# TRD.net
KiCad netlist of a schematic drawn in Altium Designer
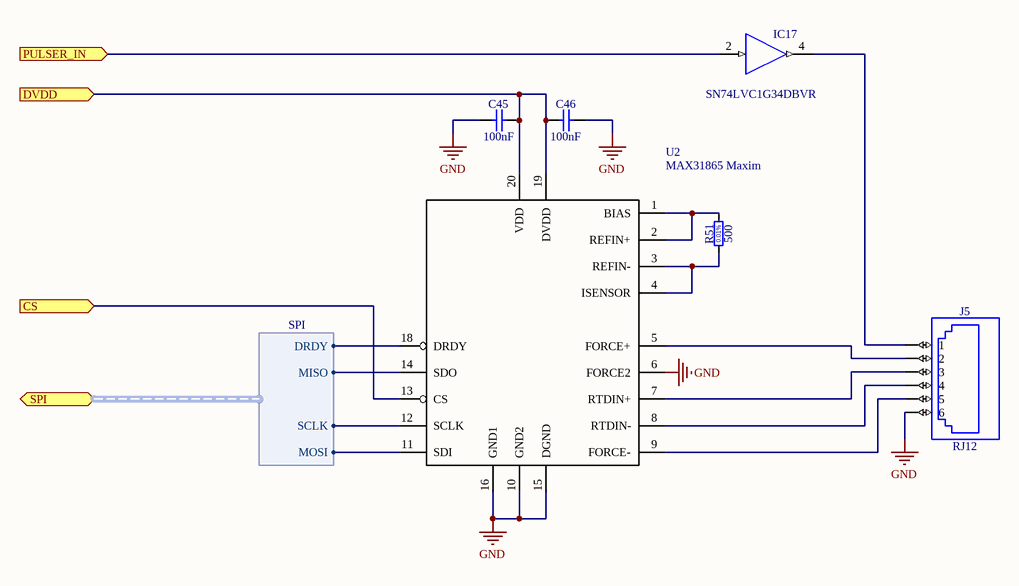
[diagram p0: TRD.SchDoc]

(export (version "E")
  (design (tool "Eeschema 10.0.6"))
  (components
    (comp (ref "C45")
      (value "100nF")
      (footprint "CAPC3216X140N")
      (description "Non-polarised capacitor")
      (fields
        (field (name "PART NUMBER") "CC1206_100NF_100V_10%_X7R")
        (field (name "VOLTAGE") "100V")
        (field (name "AUTHOR") "CERN DEM JLC")
      )
      (libsource (lib "Capacitors") (part "Capacitor - non polarized"))
    )
    (comp (ref "C46")
      (value "100nF")
      (footprint "CAPC3216X140N")
      (description "Non-polarised capacitor")
      (fields
        (field (name "PART NUMBER") "CC1206_100NF_100V_10%_X7R")
        (field (name "VOLTAGE") "100V")
        (field (name "AUTHOR") "CERN DEM JLC")
      )
      (libsource (lib "Capacitors") (part "Capacitor - non polarized"))
    )
    (comp (ref "IC17")
      (value "SN74LVC1G34DBVR")
      (footprint "SOT95P280X145-5N")
      (description "Single Buffer Gate")
      (fields (field (name "MANUFACTURER") "TEXAS INSTRUMENTS") (field (name "AUTHOR") "CERN DEM JLC"))
      (libsource (lib "ICs And Semiconductors") (part "741G34"))
    )
    (comp (ref "J5")
      (value "RJ12")
      (footprint "WURTH_615006138521")
      (description "Connector RJ12 (6P6C)")
      (fields
        (field (name "PART NUMBER") "WURTH_615006138521")
        (field (name "MANUFACTURER") "WURTH ELEKTRONIK")
        (field (name "AUTHOR") "CERN DEM MR")
      )
      (libsource (lib "Connectors") (part "Connector RJ12"))
    )
    (comp (ref "R51")
      (value "500")
      (footprint "RESC2013X64N")
      (description "Resistor - 0.01%")
      (fields
        (field (name "PART NUMBER") "R0805_500R_0.01%_0.2W_0.2PPM_VISHAY_VSMP")
        (field (name "POWER") "0.2W")
        (field (name "AUTHOR") "CERN DEM JLC")
      )
      (libsource (lib "Resistors") (part "Resistor - 0.01%"))
    )
    (comp (ref "U2")
      (value "MAX31865 Maxim")
      (fields (field (name "MANUFACTURER") "Maxim"))
      (libsource (lib "Additional") (part "MAX31865"))
    )
  )
  (nets
    (net (code "2") (name "/CS") (class "Default")
      (node (ref "U2") (pin "13") (pinfunction "CS_13") (pintype "passive"))
    )
    (net (code "3") (name "/DRDY") (class "Default")
      (node (ref "U2") (pin "18") (pinfunction "DRDY_18") (pintype "passive"))
    )
    (net (code "4") (name "/DVDD") (class "Default")
      (node (ref "C45") (pin "2") (pinfunction "2_2") (pintype "passive"))
      (node (ref "C46") (pin "1") (pinfunction "1_1") (pintype "passive"))
      (node (ref "U2") (pin "19") (pinfunction "DVDD_19") (pintype "passive"))
      (node (ref "U2") (pin "20") (pinfunction "VDD_20") (pintype "passive"))
    )
    (net (code "5") (name "/MISO") (class "Default")
      (node (ref "U2") (pin "14") (pinfunction "SDO_14") (pintype "passive"))
    )
    (net (code "6") (name "/MOSI") (class "Default")
      (node (ref "U2") (pin "11") (pinfunction "SDI_11") (pintype "passive"))
    )
    (net (code "7") (name "/PULSER_IN") (class "Default")
      (node (ref "IC17") (pin "2") (pinfunction "IN_2") (pintype "input"))
    )
    (net (code "8") (name "/SCLK") (class "Default")
      (node (ref "U2") (pin "12") (pinfunction "SCLK_12") (pintype "passive"))
    )
    (net (code "10") (name "GND") (class "Default")
      (node (ref "C45") (pin "1") (pinfunction "1_1") (pintype "passive"))
      (node (ref "C46") (pin "2") (pinfunction "2_2") (pintype "passive"))
      (node (ref "IC17") (pin "3") (pinfunction "GND_3") (pintype "power_in"))
      (node (ref "J5") (pin "6") (pinfunction "6_6") (pintype "bidirectional"))
      (node (ref "U2") (pin "10") (pinfunction "GND2_10") (pintype "passive"))
      (node (ref "U2") (pin "15") (pinfunction "DGND_15") (pintype "passive"))
      (node (ref "U2") (pin "16") (pinfunction "GND1_16") (pintype "passive"))
      (node (ref "U2") (pin "6") (pinfunction "FORCE2_6") (pintype "passive"))
    )
    (net (code "11") (name "Net-(IC17-OUT)") (class "Default")
      (node (ref "IC17") (pin "4") (pinfunction "OUT_4") (pintype "output"))
      (node (ref "J5") (pin "1") (pinfunction "1_1") (pintype "bidirectional"))
    )
    (net (code "12") (name "Net-(U2-BIAS)") (class "Default")
      (node (ref "R51") (pin "2") (pinfunction "2_2") (pintype "passive"))
      (node (ref "U2") (pin "1") (pinfunction "BIAS_1") (pintype "passive"))
      (node (ref "U2") (pin "2") (pinfunction "REFIN+_2") (pintype "passive"))
    )
    (net (code "13") (name "Net-(U2-FORCE+)") (class "Default")
      (node (ref "J5") (pin "2") (pinfunction "2_2") (pintype "bidirectional"))
      (node (ref "U2") (pin "5") (pinfunction "FORCE+_5") (pintype "passive"))
    )
    (net (code "14") (name "Net-(U2-FORCE-)") (class "Default")
      (node (ref "J5") (pin "5") (pinfunction "5_5") (pintype "bidirectional"))
      (node (ref "U2") (pin "9") (pinfunction "FORCE-_9") (pintype "passive"))
    )
    (net (code "15") (name "Net-(U2-ISENSOR)") (class "Default")
      (node (ref "R51") (pin "1") (pinfunction "1_1") (pintype "passive"))
      (node (ref "U2") (pin "3") (pinfunction "REFIN-_3") (pintype "passive"))
      (node (ref "U2") (pin "4") (pinfunction "ISENSOR_4") (pintype "passive"))
    )
    (net (code "16") (name "Net-(U2-RTDIN+)") (class "Default")
      (node (ref "J5") (pin "3") (pinfunction "3_3") (pintype "bidirectional"))
      (node (ref "U2") (pin "7") (pinfunction "RTDIN+_7") (pintype "passive"))
    )
    (net (code "17") (name "Net-(U2-RTDIN-)") (class "Default")
      (node (ref "J5") (pin "4") (pinfunction "4_4") (pintype "bidirectional"))
      (node (ref "U2") (pin "8") (pinfunction "RTDIN-_8") (pintype "passive"))
    )
    (net (code "18") (name "VCC") (class "Default")
      (node (ref "IC17") (pin "5") (pinfunction "VCC_5") (pintype "power_in"))
    )
    (net (code "19") (name "unconnected-(U2-Pad17)") (class "Default")
      (node (ref "U2") (pin "17") (pintype "passive"))
    )
  )
)
